# SIM900-SMS-Relay-Controller.net
KiCad netlist of a schematic drawn in EAGLE
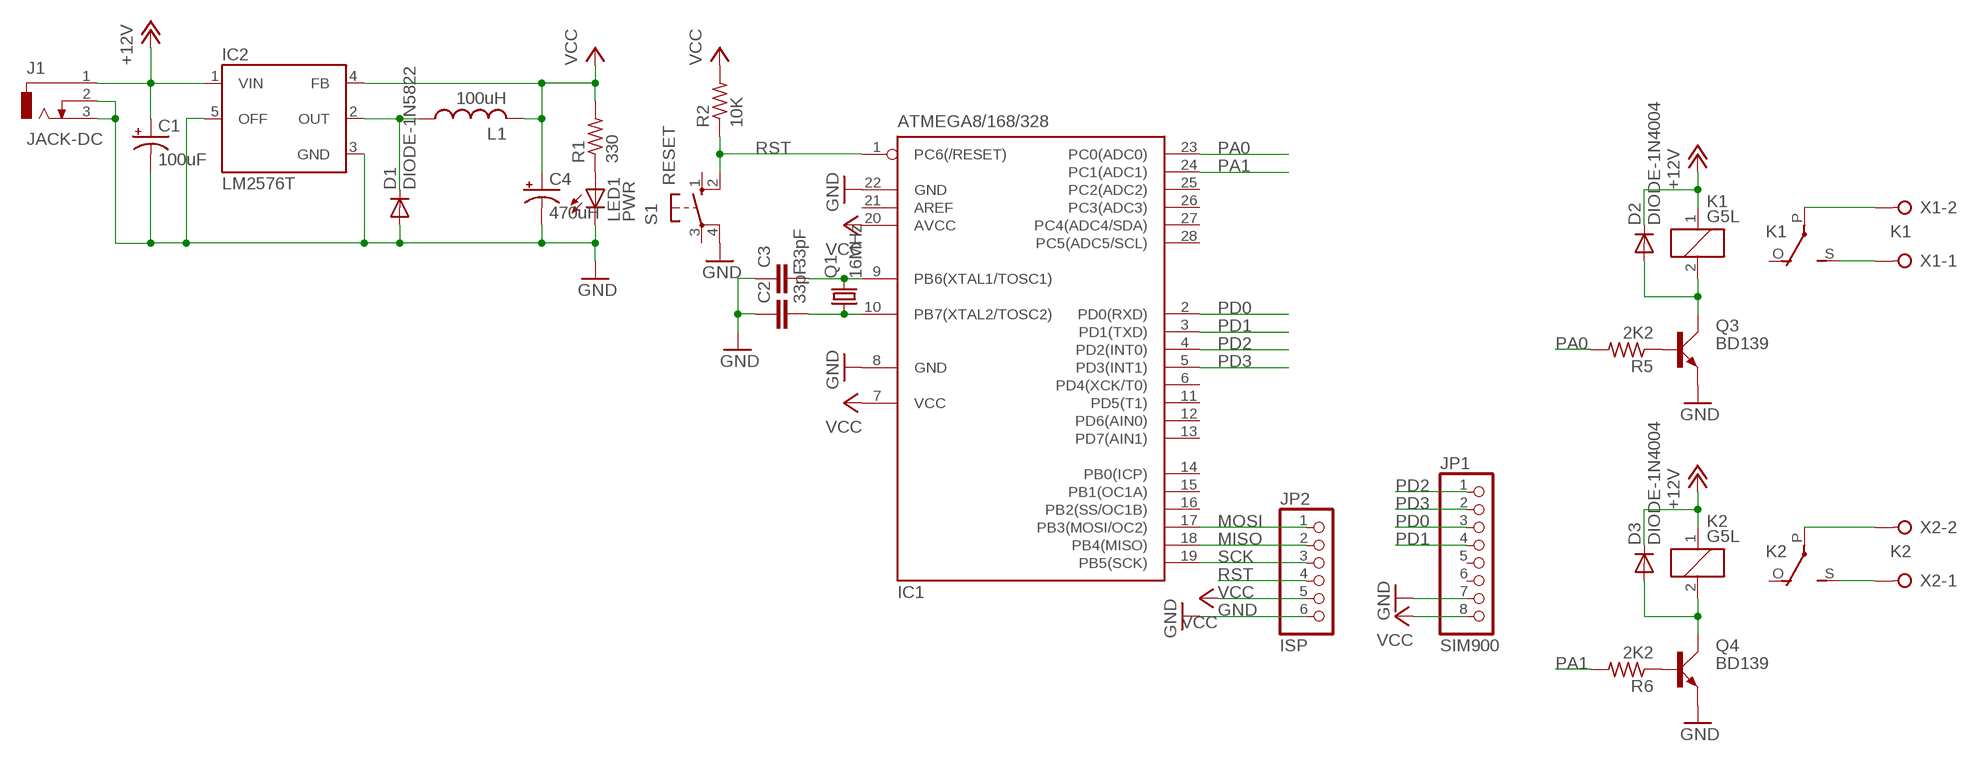
[diagram p0: schematic, sheet 1]

(export (version "E")
  (design (tool "Eeschema 10.0.6"))
  (components
    (comp (ref "C1")
      (value "100uF")
      (footprint "eagle-import:E2,5-6")
      (libsource (lib "eagle-import") (part "CAPACITOR-POLARE2.5-6"))
    )
    (comp (ref "C2")
      (value "33pF")
      (footprint "eagle-import:C025-024X044")
      (libsource (lib "eagle-import") (part "CAPACITOR-NONPOLAR025-024X044"))
    )
    (comp (ref "C3")
      (value "33pF")
      (footprint "eagle-import:C025-024X044")
      (libsource (lib "eagle-import") (part "CAPACITOR-NONPOLAR025-024X044"))
    )
    (comp (ref "C4")
      (value "470uH")
      (footprint "eagle-import:E3,5-8")
      (libsource (lib "eagle-import") (part "CAPACITOR-POLARE3.5-8"))
    )
    (comp (ref "D1")
      (value "DIODE-1N5822")
      (footprint "eagle-import:DO201-15")
      (libsource (lib "eagle-import") (part "DIODE-1N5822"))
    )
    (comp (ref "D2")
      (value "DIODE-1N4004")
      (footprint "eagle-import:DO41-10")
      (libsource (lib "eagle-import") (part "DIODE-1N4004"))
    )
    (comp (ref "D3")
      (value "DIODE-1N4004")
      (footprint "eagle-import:DO41-10")
      (libsource (lib "eagle-import") (part "DIODE-1N4004"))
    )
    (comp (ref "IC1")
      (value "ATMEGA8/168/328")
      (footprint "eagle-import:DIL28-3")
      (libsource (lib "eagle-import") (part "ATMEGA8/168/328"))
    )
    (comp (ref "IC2")
      (value "LM2576T")
      (footprint "eagle-import:TO220-5")
      (libsource (lib "eagle-import") (part "LM2576T"))
    )
    (comp (ref "J1")
      (value "JACK-DC")
      (footprint "eagle-import:DCJ0202")
      (libsource (lib "eagle-import") (part "JACK-DC"))
    )
    (comp (ref "JP1")
      (value "SIM900")
      (footprint "eagle-import:1X08")
      (libsource (lib "eagle-import") (part "PINHD-1X8"))
    )
    (comp (ref "JP2")
      (value "ISP")
      (footprint "eagle-import:1X06")
      (libsource (lib "eagle-import") (part "PINHD-1X6"))
    )
    (comp (ref "K1")
      (value "G5L")
      (footprint "eagle-import:G5LE")
      (libsource (lib "eagle-import") (part "G5L"))
    )
    (comp (ref "K2")
      (value "G5L")
      (footprint "eagle-import:G5LE")
      (libsource (lib "eagle-import") (part "G5L"))
    )
    (comp (ref "L1")
      (value "100uH")
      (footprint "eagle-import:TJ3-U2")
      (libsource (lib "eagle-import") (part "INDUCTORTJ3-U2"))
    )
    (comp (ref "LED1")
      (value "PWR")
      (footprint "eagle-import:LED3MM")
      (libsource (lib "eagle-import") (part "LED3MM"))
    )
    (comp (ref "Q1")
      (value "16MHz")
      (footprint "eagle-import:HC49_S")
      (libsource (lib "eagle-import") (part "CRYSTALHC49S"))
    )
    (comp (ref "Q3")
      (value "BD139")
      (footprint "eagle-import:TO126AV")
      (libsource (lib "eagle-import") (part "BD139"))
    )
    (comp (ref "Q4")
      (value "BD139")
      (footprint "eagle-import:TO126AV")
      (libsource (lib "eagle-import") (part "BD139"))
    )
    (comp (ref "R1")
      (value "330")
      (footprint "eagle-import:0207_10")
      (libsource (lib "eagle-import") (part "RESISTOR0207/10"))
    )
    (comp (ref "R2")
      (value "10K")
      (footprint "eagle-import:0207_10")
      (libsource (lib "eagle-import") (part "RESISTOR0207/10"))
    )
    (comp (ref "R5")
      (value "2K2")
      (footprint "eagle-import:0207_10")
      (libsource (lib "eagle-import") (part "RESISTOR0207/10"))
    )
    (comp (ref "R6")
      (value "2K2")
      (footprint "eagle-import:0207_10")
      (libsource (lib "eagle-import") (part "RESISTOR0207/10"))
    )
    (comp (ref "S1")
      (value "RESET")
      (footprint "eagle-import:B3F-10XX")
      (fields (field (name "MPN") "B3F-1000"))
      (libsource (lib "eagle-import") (part "SW-PUSHBUTTON"))
    )
    (comp (ref "X1")
      (value "K1")
      (footprint "eagle-import:W237-132")
      (libsource (lib "eagle-import") (part "W237-02P"))
    )
    (comp (ref "X2")
      (value "K2")
      (footprint "eagle-import:W237-132")
      (libsource (lib "eagle-import") (part "W237-02P"))
    )
  )
  (nets
    (net (code "1") (name "+12V") (class "Default")
      (node (ref "C1") (pin "+") (pinfunction "+_+") (pintype "passive"))
      (node (ref "D2") (pin "C") (pinfunction "C_C") (pintype "passive"))
      (node (ref "D3") (pin "C") (pinfunction "C_C") (pintype "passive"))
      (node (ref "IC2") (pin "1") (pinfunction "VIN_1") (pintype "power_in"))
      (node (ref "J1") (pin "1") (pinfunction "1_1") (pintype "passive"))
      (node (ref "K1") (pin "1") (pinfunction "1_1") (pintype "passive"))
      (node (ref "K2") (pin "1") (pinfunction "1_1") (pintype "passive"))
    )
    (net (code "2") (name "/MISO") (class "Default")
      (node (ref "IC1") (pin "18") (pinfunction "PB4(MISO)_18") (pintype "bidirectional"))
      (node (ref "JP2") (pin "2") (pinfunction "2_2") (pintype "passive"))
    )
    (net (code "3") (name "/MOSI") (class "Default")
      (node (ref "IC1") (pin "17") (pinfunction "PB3(MOSI/OC2)_17") (pintype "bidirectional"))
      (node (ref "JP2") (pin "1") (pinfunction "1_1") (pintype "passive"))
    )
    (net (code "4") (name "/PA0") (class "Default")
      (node (ref "IC1") (pin "23") (pinfunction "PC0(ADC0)_23") (pintype "bidirectional"))
      (node (ref "R5") (pin "2") (pinfunction "2_2") (pintype "passive"))
    )
    (net (code "5") (name "/PA1") (class "Default")
      (node (ref "IC1") (pin "24") (pinfunction "PC1(ADC1)_24") (pintype "bidirectional"))
      (node (ref "R6") (pin "2") (pinfunction "2_2") (pintype "passive"))
    )
    (net (code "6") (name "/PD0") (class "Default")
      (node (ref "IC1") (pin "2") (pinfunction "PD0(RXD)_2") (pintype "bidirectional"))
      (node (ref "JP1") (pin "3") (pinfunction "3_3") (pintype "passive"))
    )
    (net (code "7") (name "/PD1") (class "Default")
      (node (ref "IC1") (pin "3") (pinfunction "PD1(TXD)_3") (pintype "bidirectional"))
      (node (ref "JP1") (pin "4") (pinfunction "4_4") (pintype "passive"))
    )
    (net (code "8") (name "/PD2") (class "Default")
      (node (ref "IC1") (pin "4") (pinfunction "PD2(INT0)_4") (pintype "bidirectional"))
      (node (ref "JP1") (pin "1") (pinfunction "1_1") (pintype "passive"))
    )
    (net (code "9") (name "/PD3") (class "Default")
      (node (ref "IC1") (pin "5") (pinfunction "PD3(INT1)_5") (pintype "bidirectional"))
      (node (ref "JP1") (pin "2") (pinfunction "2_2") (pintype "passive"))
    )
    (net (code "10") (name "/RST") (class "Default")
      (node (ref "IC1") (pin "1") (pinfunction "PC6(/RESET)_1") (pintype "bidirectional"))
      (node (ref "JP2") (pin "4") (pinfunction "4_4") (pintype "passive"))
      (node (ref "R2") (pin "1") (pinfunction "1_1") (pintype "passive"))
      (node (ref "S1") (pin "2") (pinfunction "S1_2") (pintype "passive"))
    )
    (net (code "11") (name "/SCK") (class "Default")
      (node (ref "IC1") (pin "19") (pinfunction "PB5(SCK)_19") (pintype "bidirectional"))
      (node (ref "JP2") (pin "3") (pinfunction "3_3") (pintype "passive"))
    )
    (net (code "12") (name "GND") (class "Default")
      (node (ref "C1") (pin "-") (pinfunction "-_-") (pintype "passive"))
      (node (ref "C2") (pin "1") (pinfunction "1_1") (pintype "passive"))
      (node (ref "C3") (pin "1") (pinfunction "1_1") (pintype "passive"))
      (node (ref "C4") (pin "-") (pinfunction "-_-") (pintype "passive"))
      (node (ref "D1") (pin "A") (pinfunction "A_A") (pintype "passive"))
      (node (ref "IC1") (pin "22") (pinfunction "GND_22") (pintype "power_in"))
      (node (ref "IC1") (pin "8") (pinfunction "GND_8") (pintype "power_in"))
      (node (ref "IC2") (pin "3") (pinfunction "GND_3") (pintype "power_in"))
      (node (ref "IC2") (pin "5") (pinfunction "OFF_5") (pintype "input"))
      (node (ref "J1") (pin "2") (pinfunction "2_2") (pintype "passive"))
      (node (ref "J1") (pin "3") (pinfunction "3_3") (pintype "passive"))
      (node (ref "JP1") (pin "7") (pinfunction "7_7") (pintype "passive"))
      (node (ref "JP2") (pin "6") (pinfunction "6_6") (pintype "passive"))
      (node (ref "LED1") (pin "K") (pinfunction "C_K") (pintype "passive"))
      (node (ref "Q3") (pin "E") (pinfunction "E_E") (pintype "passive"))
      (node (ref "Q4") (pin "E") (pinfunction "E_E") (pintype "passive"))
      (node (ref "S1") (pin "4") (pinfunction "P1_4") (pintype "passive"))
    )
    (net (code "13") (name "Net-(D2-PadA)") (class "Default")
      (node (ref "D2") (pin "A") (pinfunction "A_A") (pintype "passive"))
      (node (ref "K1") (pin "2") (pinfunction "2_2") (pintype "passive"))
      (node (ref "Q3") (pin "C") (pinfunction "C_C") (pintype "passive"))
    )
    (net (code "14") (name "Net-(D3-PadA)") (class "Default")
      (node (ref "D3") (pin "A") (pinfunction "A_A") (pintype "passive"))
      (node (ref "K2") (pin "2") (pinfunction "2_2") (pintype "passive"))
      (node (ref "Q4") (pin "C") (pinfunction "C_C") (pintype "passive"))
    )
    (net (code "15") (name "Net-(IC1-PB6(XTAL1{slash}TOSC1))") (class "Default")
      (node (ref "C3") (pin "2") (pinfunction "2_2") (pintype "passive"))
      (node (ref "IC1") (pin "9") (pinfunction "PB6(XTAL1/TOSC1)_9") (pintype "bidirectional"))
      (node (ref "Q1") (pin "2") (pinfunction "2_2") (pintype "passive"))
    )
    (net (code "16") (name "Net-(IC1-PB7(XTAL2{slash}TOSC2))") (class "Default")
      (node (ref "C2") (pin "2") (pinfunction "2_2") (pintype "passive"))
      (node (ref "IC1") (pin "10") (pinfunction "PB7(XTAL2/TOSC2)_10") (pintype "bidirectional"))
      (node (ref "Q1") (pin "1") (pinfunction "1_1") (pintype "passive"))
    )
    (net (code "17") (name "Net-(IC2-OUT)") (class "Default")
      (node (ref "D1") (pin "C") (pinfunction "C_C") (pintype "passive"))
      (node (ref "IC2") (pin "2") (pinfunction "OUT_2") (pintype "output"))
      (node (ref "L1") (pin "1") (pinfunction "1_1") (pintype "passive"))
    )
    (net (code "18") (name "Net-(LED1-PadA)") (class "Default")
      (node (ref "LED1") (pin "A") (pinfunction "A_A") (pintype "passive"))
      (node (ref "R1") (pin "1") (pinfunction "1_1") (pintype "passive"))
    )
    (net (code "19") (name "Net-(Q3-PadB)") (class "Default")
      (node (ref "Q3") (pin "B") (pinfunction "B_B") (pintype "passive"))
      (node (ref "R5") (pin "1") (pinfunction "1_1") (pintype "passive"))
    )
    (net (code "20") (name "Net-(Q4-PadB)") (class "Default")
      (node (ref "Q4") (pin "B") (pinfunction "B_B") (pintype "passive"))
      (node (ref "R6") (pin "1") (pinfunction "1_1") (pintype "passive"))
    )
    (net (code "21") (name "Net-(X1A-KL)") (class "Default")
      (node (ref "K1") (pin "S") (pinfunction "S_S") (pintype "passive"))
      (node (ref "X1") (pin "1") (pinfunction "KL_1") (pintype "passive"))
    )
    (net (code "22") (name "Net-(X1B-KL)") (class "Default")
      (node (ref "K1") (pin "P") (pinfunction "P_P") (pintype "passive"))
      (node (ref "X1") (pin "2") (pinfunction "KL_2") (pintype "passive"))
    )
    (net (code "23") (name "Net-(X2A-KL)") (class "Default")
      (node (ref "K2") (pin "S") (pinfunction "S_S") (pintype "passive"))
      (node (ref "X2") (pin "1") (pinfunction "KL_1") (pintype "passive"))
    )
    (net (code "24") (name "Net-(X2B-KL)") (class "Default")
      (node (ref "K2") (pin "P") (pinfunction "P_P") (pintype "passive"))
      (node (ref "X2") (pin "2") (pinfunction "KL_2") (pintype "passive"))
    )
    (net (code "25") (name "VCC") (class "Default")
      (node (ref "C4") (pin "+") (pinfunction "+_+") (pintype "passive"))
      (node (ref "IC1") (pin "20") (pinfunction "AVCC_20") (pintype "power_in"))
      (node (ref "IC1") (pin "7") (pinfunction "VCC_7") (pintype "power_in"))
      (node (ref "IC2") (pin "4") (pinfunction "FB_4") (pintype "input"))
      (node (ref "JP1") (pin "8") (pinfunction "8_8") (pintype "passive"))
      (node (ref "JP2") (pin "5") (pinfunction "5_5") (pintype "passive"))
      (node (ref "L1") (pin "2") (pinfunction "2_2") (pintype "passive"))
      (node (ref "R1") (pin "2") (pinfunction "2_2") (pintype "passive"))
      (node (ref "R2") (pin "2") (pinfunction "2_2") (pintype "passive"))
    )
    (net (code "26") (name "unconnected-(IC1-AREF-Pad21)") (class "Default")
      (node (ref "IC1") (pin "21") (pinfunction "AREF_21") (pintype "passive"))
    )
    (net (code "27") (name "unconnected-(IC1-PB0(ICP)-Pad14)") (class "Default")
      (node (ref "IC1") (pin "14") (pinfunction "PB0(ICP)_14") (pintype "bidirectional"))
    )
    (net (code "28") (name "unconnected-(IC1-PB1(OC1A)-Pad15)") (class "Default")
      (node (ref "IC1") (pin "15") (pinfunction "PB1(OC1A)_15") (pintype "bidirectional"))
    )
    (net (code "29") (name "unconnected-(IC1-PB2(SS{slash}OC1B)-Pad16)") (class "Default")
      (node (ref "IC1") (pin "16") (pinfunction "PB2(SS/OC1B)_16") (pintype "bidirectional"))
    )
    (net (code "30") (name "unconnected-(IC1-PC2(ADC2)-Pad25)") (class "Default")
      (node (ref "IC1") (pin "25") (pinfunction "PC2(ADC2)_25") (pintype "bidirectional"))
    )
    (net (code "31") (name "unconnected-(IC1-PC3(ADC3)-Pad26)") (class "Default")
      (node (ref "IC1") (pin "26") (pinfunction "PC3(ADC3)_26") (pintype "bidirectional"))
    )
    (net (code "32") (name "unconnected-(IC1-PC4(ADC4{slash}SDA)-Pad27)") (class "Default")
      (node (ref "IC1") (pin "27") (pinfunction "PC4(ADC4/SDA)_27") (pintype "bidirectional"))
    )
    (net (code "33") (name "unconnected-(IC1-PC5(ADC5{slash}SCL)-Pad28)") (class "Default")
      (node (ref "IC1") (pin "28") (pinfunction "PC5(ADC5/SCL)_28") (pintype "bidirectional"))
    )
    (net (code "34") (name "unconnected-(IC1-PD4(XCK{slash}T0)-Pad6)") (class "Default")
      (node (ref "IC1") (pin "6") (pinfunction "PD4(XCK/T0)_6") (pintype "bidirectional"))
    )
    (net (code "35") (name "unconnected-(IC1-PD5(T1)-Pad11)") (class "Default")
      (node (ref "IC1") (pin "11") (pinfunction "PD5(T1)_11") (pintype "bidirectional"))
    )
    (net (code "36") (name "unconnected-(IC1-PD6(AIN0)-Pad12)") (class "Default")
      (node (ref "IC1") (pin "12") (pinfunction "PD6(AIN0)_12") (pintype "bidirectional"))
    )
    (net (code "37") (name "unconnected-(IC1-PD7(AIN1)-Pad13)") (class "Default")
      (node (ref "IC1") (pin "13") (pinfunction "PD7(AIN1)_13") (pintype "bidirectional"))
    )
    (net (code "38") (name "unconnected-(JP1-Pad5)") (class "Default")
      (node (ref "JP1") (pin "5") (pinfunction "5_5") (pintype "passive"))
    )
    (net (code "39") (name "unconnected-(JP1-Pad6)") (class "Default")
      (node (ref "JP1") (pin "6") (pinfunction "6_6") (pintype "passive"))
    )
    (net (code "40") (name "unconnected-(K1-PadO)") (class "Default")
      (node (ref "K1") (pin "O") (pinfunction "O_O") (pintype "passive"))
    )
    (net (code "41") (name "unconnected-(K2-PadO)") (class "Default")
      (node (ref "K2") (pin "O") (pinfunction "O_O") (pintype "passive"))
    )
    (net (code "42") (name "unconnected-(S1-P-Pad3)") (class "Default")
      (node (ref "S1") (pin "3") (pinfunction "P_3") (pintype "passive"))
    )
    (net (code "43") (name "unconnected-(S1-S-Pad1)") (class "Default")
      (node (ref "S1") (pin "1") (pinfunction "S_1") (pintype "passive"))
    )
  )
)
